# sensorNodev4.net
KiCad netlist of a schematic drawn in EAGLE
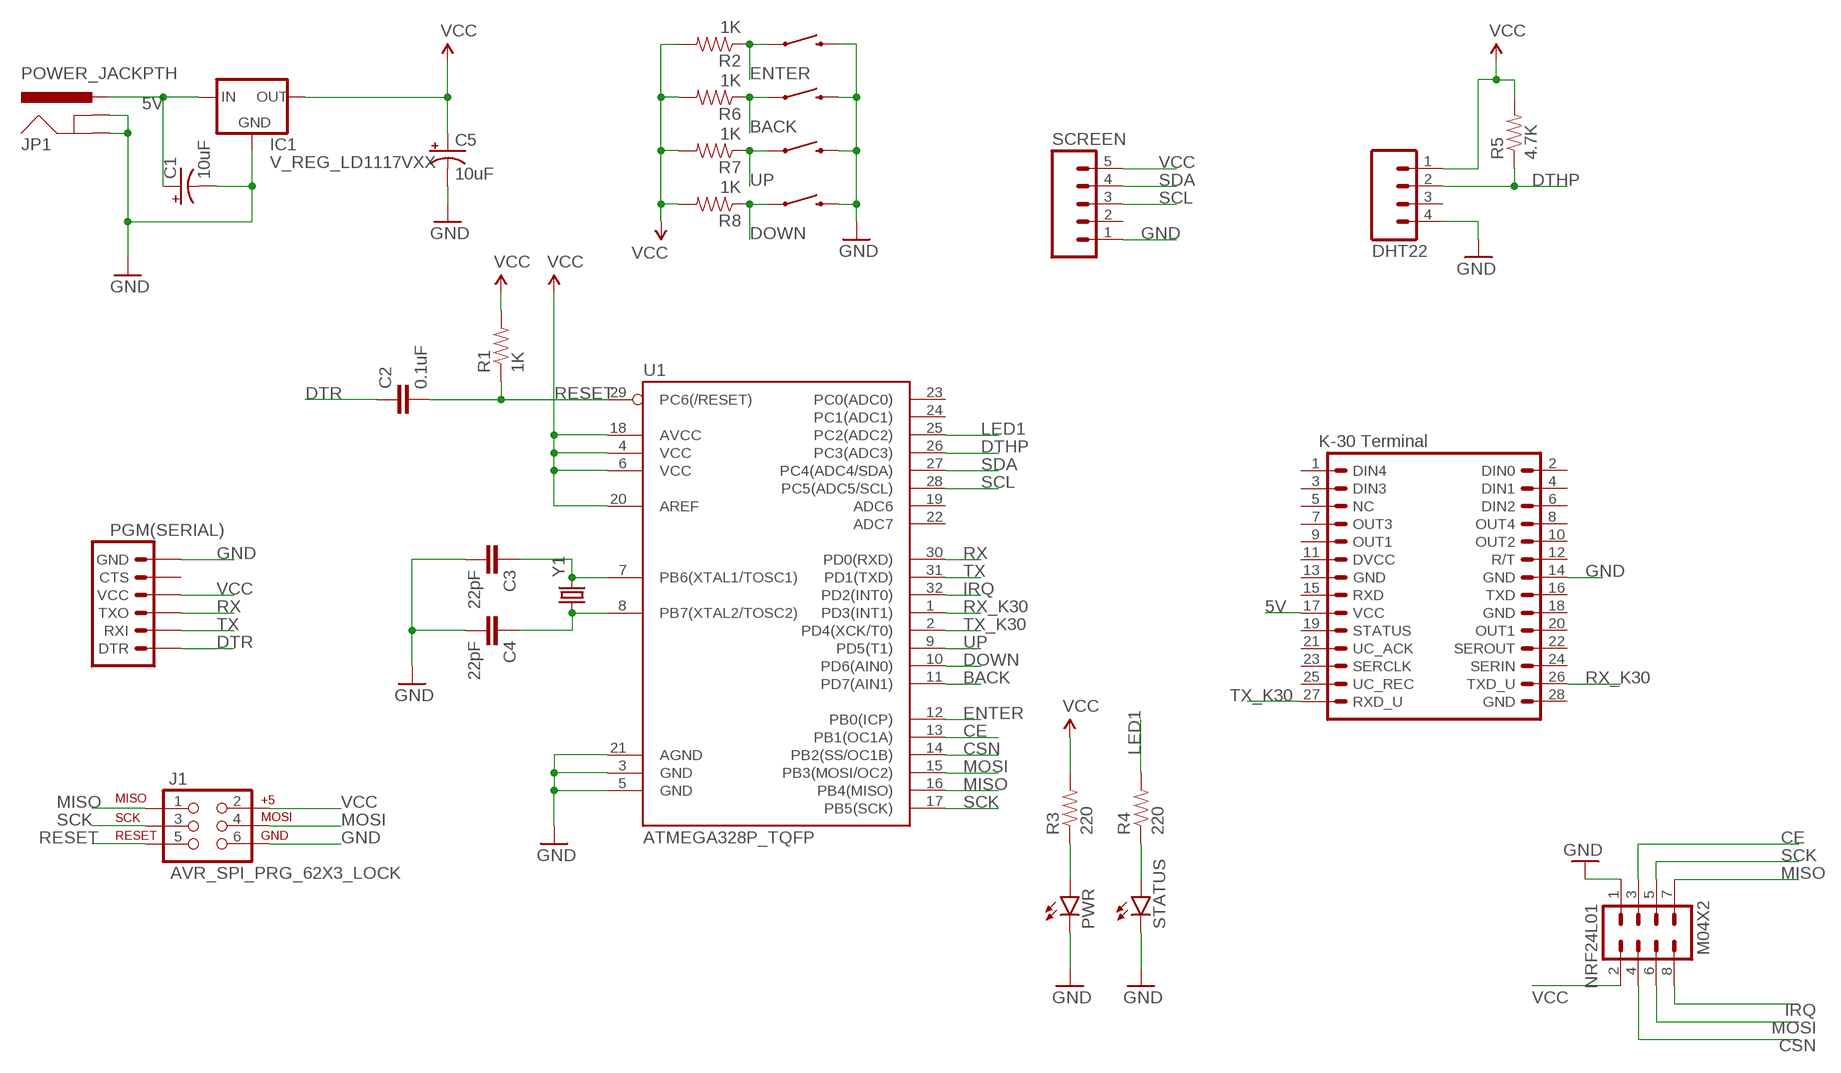
[diagram p0: schematic, sheet 1]

(export (version "E")
  (design (tool "Eeschema 10.0.6"))
  (components
    (comp (ref "BACK")
      (value "SWITCH-MOMENTARY-2PTH")
      (footprint "eagle-import:TACTILE-PTH")
      (libsource (lib "eagle-import") (part "SWITCH-MOMENTARY-2PTH"))
    )
    (comp (ref "C1")
      (value "10uF")
      (footprint "eagle-import:CPOL-RADIAL-10UF-25V")
      (libsource (lib "eagle-import") (part "CAP_POLPTH2"))
    )
    (comp (ref "C2")
      (value "0.1uF")
      (footprint "eagle-import:0603-CAP")
      (libsource (lib "eagle-import") (part "0.1UF-25V(+80/-20%)(0603)"))
    )
    (comp (ref "C3")
      (value "22pF")
      (footprint "eagle-import:0603-CAP")
      (libsource (lib "eagle-import") (part "22PF-50V-5%(0603)"))
    )
    (comp (ref "C4")
      (value "22pF")
      (footprint "eagle-import:0603-CAP")
      (libsource (lib "eagle-import") (part "22PF-50V-5%(0603)"))
    )
    (comp (ref "C5")
      (value "10uF")
      (footprint "eagle-import:CPOL-RADIAL-10UF-25V")
      (libsource (lib "eagle-import") (part "CAP_POLPTH2"))
    )
    (comp (ref "DHT22")
      (value "M04PTH")
      (footprint "eagle-import:1X04")
      (libsource (lib "eagle-import") (part "M04PTH"))
    )
    (comp (ref "DOWN")
      (value "SWITCH-MOMENTARY-2PTH")
      (footprint "eagle-import:TACTILE-PTH")
      (libsource (lib "eagle-import") (part "SWITCH-MOMENTARY-2PTH"))
    )
    (comp (ref "ENTER")
      (value "SWITCH-MOMENTARY-2PTH")
      (footprint "eagle-import:TACTILE-PTH")
      (libsource (lib "eagle-import") (part "SWITCH-MOMENTARY-2PTH"))
    )
    (comp (ref "IC1")
      (value "V_REG_LD1117VXX")
      (footprint "eagle-import:78XXL")
      (libsource (lib "eagle-import") (part "V_REG_LD1117VXX"))
    )
    (comp (ref "J1")
      (value "AVR_SPI_PRG_62X3_LOCK")
      (footprint "eagle-import:2X3_LOCK")
      (libsource (lib "eagle-import") (part "AVR_SPI_PRG_62X3_LOCK"))
    )
    (comp (ref "JP1")
      (value "POWER_JACKPTH")
      (footprint "eagle-import:POWER_JACK_PTH")
      (libsource (lib "eagle-import") (part "POWER_JACKPTH"))
    )
    (comp (ref "JP3")
      (value "K-30K-30")
      (footprint "eagle-import:K-30")
      (libsource (lib "eagle-import") (part "K-30K-30"))
    )
    (comp (ref "NRF24L01")
      (value "M04X2")
      (footprint "eagle-import:2X4")
      (libsource (lib "eagle-import") (part "M04X2"))
    )
    (comp (ref "PGM(SERIAL)")
      (value "ARDUINO_SERIAL_PROGRAMPTH")
      (footprint "eagle-import:1X06")
      (libsource (lib "eagle-import") (part "ARDUINO_SERIAL_PROGRAMPTH"))
    )
    (comp (ref "PWR")
      (value "LED0603")
      (footprint "eagle-import:LED-0603")
      (libsource (lib "eagle-import") (part "LED0603"))
    )
    (comp (ref "R1")
      (value "1K")
      (footprint "eagle-import:0603-RES")
      (libsource (lib "eagle-import") (part "1KOHM-1/10W-1%(0603)"))
    )
    (comp (ref "R2")
      (value "1K")
      (footprint "eagle-import:0603-RES")
      (libsource (lib "eagle-import") (part "1KOHM-1/10W-1%(0603)"))
    )
    (comp (ref "R3")
      (value "220")
      (footprint "eagle-import:0603-RES")
      (libsource (lib "eagle-import") (part "1KOHM-1/10W-1%(0603)"))
    )
    (comp (ref "R4")
      (value "220")
      (footprint "eagle-import:0603-RES")
      (libsource (lib "eagle-import") (part "1KOHM-1/10W-1%(0603)"))
    )
    (comp (ref "R5")
      (value "4.7K")
      (footprint "eagle-import:0603-RES")
      (libsource (lib "eagle-import") (part "1KOHM-1/10W-1%(0603)"))
    )
    (comp (ref "R6")
      (value "1K")
      (footprint "eagle-import:0603-RES")
      (libsource (lib "eagle-import") (part "1KOHM-1/10W-1%(0603)"))
    )
    (comp (ref "R7")
      (value "1K")
      (footprint "eagle-import:0603-RES")
      (libsource (lib "eagle-import") (part "1KOHM-1/10W-1%(0603)"))
    )
    (comp (ref "R8")
      (value "1K")
      (footprint "eagle-import:0603-RES")
      (libsource (lib "eagle-import") (part "1KOHM-1/10W-1%(0603)"))
    )
    (comp (ref "SCREEN")
      (value "M05PTH")
      (footprint "eagle-import:1X05")
      (libsource (lib "eagle-import") (part "M05PTH"))
    )
    (comp (ref "STATUS")
      (value "LED0603")
      (footprint "eagle-import:LED-0603")
      (libsource (lib "eagle-import") (part "LED0603"))
    )
    (comp (ref "U1")
      (value "ATMEGA328P_TQFP")
      (footprint "eagle-import:TQFP32-08")
      (libsource (lib "eagle-import") (part "ATMEGA328P_TQFP"))
    )
    (comp (ref "UP")
      (value "SWITCH-MOMENTARY-2PTH")
      (footprint "eagle-import:TACTILE-PTH")
      (libsource (lib "eagle-import") (part "SWITCH-MOMENTARY-2PTH"))
    )
    (comp (ref "Y1")
      (value "CRYSTALHC49US")
      (footprint "eagle-import:HC49US")
      (libsource (lib "eagle-import") (part "CRYSTALHC49US"))
    )
  )
  (nets
    (net (code "1") (name "/5V") (class "Default")
      (node (ref "C1") (pin "1") (pinfunction "+_1") (pintype "passive"))
      (node (ref "IC1") (pin "OUT") (pinfunction "IN_OUT") (pintype "input"))
      (node (ref "JP1") (pin "PWR") (pinfunction "PWR_PWR") (pintype "bidirectional"))
      (node (ref "JP3") (pin "17") (pinfunction "VCC_17") (pintype "bidirectional"))
    )
    (net (code "2") (name "/BACK") (class "Default")
      (node (ref "BACK") (pin "1") (pinfunction "1_1") (pintype "passive"))
      (node (ref "R6") (pin "1") (pinfunction "1_1") (pintype "passive"))
      (node (ref "U1") (pin "11") (pinfunction "PD7(AIN1)_11") (pintype "bidirectional"))
    )
    (net (code "3") (name "/CE") (class "Default")
      (node (ref "NRF24L01") (pin "3") (pinfunction "3_3") (pintype "passive"))
      (node (ref "U1") (pin "13") (pinfunction "PB1(OC1A)_13") (pintype "bidirectional"))
    )
    (net (code "4") (name "/CSN") (class "Default")
      (node (ref "NRF24L01") (pin "4") (pinfunction "4_4") (pintype "passive"))
      (node (ref "U1") (pin "14") (pinfunction "PB2(SS/OC1B)_14") (pintype "bidirectional"))
    )
    (net (code "5") (name "/DOWN") (class "Default")
      (node (ref "DOWN") (pin "1") (pinfunction "1_1") (pintype "passive"))
      (node (ref "R8") (pin "1") (pinfunction "1_1") (pintype "passive"))
      (node (ref "U1") (pin "10") (pinfunction "PD6(AIN0)_10") (pintype "bidirectional"))
    )
    (net (code "6") (name "/DTHP") (class "Default")
      (node (ref "DHT22") (pin "2") (pinfunction "2_2") (pintype "passive"))
      (node (ref "R5") (pin "1") (pinfunction "1_1") (pintype "passive"))
      (node (ref "U1") (pin "26") (pinfunction "PC3(ADC3)_26") (pintype "bidirectional"))
    )
    (net (code "7") (name "/DTR") (class "Default")
      (node (ref "C2") (pin "1") (pinfunction "1_1") (pintype "passive"))
      (node (ref "PGM(SERIAL)") (pin "1") (pinfunction "DTR_1") (pintype "passive"))
    )
    (net (code "8") (name "/ENTER") (class "Default")
      (node (ref "ENTER") (pin "1") (pinfunction "1_1") (pintype "passive"))
      (node (ref "R2") (pin "1") (pinfunction "1_1") (pintype "passive"))
      (node (ref "U1") (pin "12") (pinfunction "PB0(ICP)_12") (pintype "bidirectional"))
    )
    (net (code "9") (name "/IRQ") (class "Default")
      (node (ref "NRF24L01") (pin "8") (pinfunction "8_8") (pintype "passive"))
      (node (ref "U1") (pin "32") (pinfunction "PD2(INT0)_32") (pintype "bidirectional"))
    )
    (net (code "10") (name "/LED1") (class "Default")
      (node (ref "R4") (pin "2") (pinfunction "2_2") (pintype "passive"))
      (node (ref "U1") (pin "25") (pinfunction "PC2(ADC2)_25") (pintype "bidirectional"))
    )
    (net (code "11") (name "/MISO") (class "Default")
      (node (ref "J1") (pin "1") (pinfunction "1_1") (pintype "passive"))
      (node (ref "NRF24L01") (pin "7") (pinfunction "7_7") (pintype "passive"))
      (node (ref "U1") (pin "16") (pinfunction "PB4(MISO)_16") (pintype "bidirectional"))
    )
    (net (code "12") (name "/MOSI") (class "Default")
      (node (ref "J1") (pin "4") (pinfunction "4_4") (pintype "passive"))
      (node (ref "NRF24L01") (pin "6") (pinfunction "6_6") (pintype "passive"))
      (node (ref "U1") (pin "15") (pinfunction "PB3(MOSI/OC2)_15") (pintype "bidirectional"))
    )
    (net (code "13") (name "/RESET") (class "Default")
      (node (ref "C2") (pin "2") (pinfunction "2_2") (pintype "passive"))
      (node (ref "J1") (pin "5") (pinfunction "5_5") (pintype "passive"))
      (node (ref "R1") (pin "1") (pinfunction "1_1") (pintype "passive"))
      (node (ref "U1") (pin "29") (pinfunction "PC6(/RESET)_29") (pintype "bidirectional"))
    )
    (net (code "14") (name "/RX") (class "Default")
      (node (ref "PGM(SERIAL)") (pin "3") (pinfunction "TXO_3") (pintype "passive"))
      (node (ref "U1") (pin "30") (pinfunction "PD0(RXD)_30") (pintype "bidirectional"))
    )
    (net (code "15") (name "/RX_K30") (class "Default")
      (node (ref "JP3") (pin "26") (pinfunction "TXD_U_26") (pintype "bidirectional"))
      (node (ref "U1") (pin "1") (pinfunction "PD3(INT1)_1") (pintype "bidirectional"))
    )
    (net (code "16") (name "/SCK") (class "Default")
      (node (ref "J1") (pin "3") (pinfunction "3_3") (pintype "passive"))
      (node (ref "NRF24L01") (pin "5") (pinfunction "5_5") (pintype "passive"))
      (node (ref "U1") (pin "17") (pinfunction "PB5(SCK)_17") (pintype "bidirectional"))
    )
    (net (code "17") (name "/SCL") (class "Default")
      (node (ref "SCREEN") (pin "3") (pinfunction "3_3") (pintype "passive"))
      (node (ref "U1") (pin "28") (pinfunction "PC5(ADC5/SCL)_28") (pintype "bidirectional"))
    )
    (net (code "18") (name "/SDA") (class "Default")
      (node (ref "SCREEN") (pin "4") (pinfunction "4_4") (pintype "passive"))
      (node (ref "U1") (pin "27") (pinfunction "PC4(ADC4/SDA)_27") (pintype "bidirectional"))
    )
    (net (code "19") (name "/TX") (class "Default")
      (node (ref "PGM(SERIAL)") (pin "2") (pinfunction "RXI_2") (pintype "passive"))
      (node (ref "U1") (pin "31") (pinfunction "PD1(TXD)_31") (pintype "bidirectional"))
    )
    (net (code "20") (name "/TX_K30") (class "Default")
      (node (ref "JP3") (pin "27") (pinfunction "RXD_U_27") (pintype "bidirectional"))
      (node (ref "U1") (pin "2") (pinfunction "PD4(XCK/T0)_2") (pintype "bidirectional"))
    )
    (net (code "21") (name "/UP") (class "Default")
      (node (ref "R7") (pin "1") (pinfunction "1_1") (pintype "passive"))
      (node (ref "U1") (pin "9") (pinfunction "PD5(T1)_9") (pintype "bidirectional"))
      (node (ref "UP") (pin "1") (pinfunction "1_1") (pintype "passive"))
    )
    (net (code "22") (name "GND") (class "Default")
      (node (ref "BACK") (pin "3") (pinfunction "2_3") (pintype "passive"))
      (node (ref "C1") (pin "2") (pinfunction "-_2") (pintype "passive"))
      (node (ref "C3") (pin "2") (pinfunction "2_2") (pintype "passive"))
      (node (ref "C4") (pin "2") (pinfunction "2_2") (pintype "passive"))
      (node (ref "C5") (pin "2") (pinfunction "-_2") (pintype "passive"))
      (node (ref "DHT22") (pin "4") (pinfunction "4_4") (pintype "passive"))
      (node (ref "DOWN") (pin "3") (pinfunction "2_3") (pintype "passive"))
      (node (ref "ENTER") (pin "3") (pinfunction "2_3") (pintype "passive"))
      (node (ref "IC1") (pin "IN") (pinfunction "GND_IN") (pintype "input"))
      (node (ref "J1") (pin "6") (pinfunction "6_6") (pintype "passive"))
      (node (ref "JP1") (pin "GND") (pinfunction "GND_GND") (pintype "bidirectional"))
      (node (ref "JP1") (pin "GNDBREAK") (pinfunction "GNDBREAK_GNDBREAK") (pintype "bidirectional"))
      (node (ref "JP3") (pin "14") (pinfunction "GND_14") (pintype "bidirectional"))
      (node (ref "NRF24L01") (pin "1") (pinfunction "1_1") (pintype "passive"))
      (node (ref "PGM(SERIAL)") (pin "6") (pinfunction "GND_6") (pintype "passive"))
      (node (ref "PWR") (pin "C") (pinfunction "C_C") (pintype "passive"))
      (node (ref "SCREEN") (pin "1") (pinfunction "1_1") (pintype "passive"))
      (node (ref "STATUS") (pin "C") (pinfunction "C_C") (pintype "passive"))
      (node (ref "U1") (pin "21") (pinfunction "AGND_21") (pintype "bidirectional"))
      (node (ref "U1") (pin "3") (pinfunction "GND_3") (pintype "bidirectional"))
      (node (ref "U1") (pin "5") (pinfunction "GND_5") (pintype "bidirectional"))
      (node (ref "UP") (pin "3") (pinfunction "2_3") (pintype "passive"))
    )
    (net (code "23") (name "Net-(PWR-PadA)") (class "Default")
      (node (ref "PWR") (pin "A") (pinfunction "A_A") (pintype "passive"))
      (node (ref "R3") (pin "1") (pinfunction "1_1") (pintype "passive"))
    )
    (net (code "24") (name "Net-(R4-Pad1)") (class "Default")
      (node (ref "R4") (pin "1") (pinfunction "1_1") (pintype "passive"))
      (node (ref "STATUS") (pin "A") (pinfunction "A_A") (pintype "passive"))
    )
    (net (code "25") (name "Net-(U1-PB6(XTAL1{slash}TOSC1))") (class "Default")
      (node (ref "C3") (pin "1") (pinfunction "1_1") (pintype "passive"))
      (node (ref "U1") (pin "7") (pinfunction "PB6(XTAL1/TOSC1)_7") (pintype "bidirectional"))
      (node (ref "Y1") (pin "2") (pinfunction "2_2") (pintype "passive"))
    )
    (net (code "26") (name "Net-(U1-PB7(XTAL2{slash}TOSC2))") (class "Default")
      (node (ref "C4") (pin "1") (pinfunction "1_1") (pintype "passive"))
      (node (ref "U1") (pin "8") (pinfunction "PB7(XTAL2/TOSC2)_8") (pintype "bidirectional"))
      (node (ref "Y1") (pin "1") (pinfunction "1_1") (pintype "passive"))
    )
    (net (code "27") (name "VCC") (class "Default")
      (node (ref "C5") (pin "1") (pinfunction "+_1") (pintype "passive"))
      (node (ref "DHT22") (pin "1") (pinfunction "1_1") (pintype "passive"))
      (node (ref "IC1") (pin "GND") (pinfunction "OUT_GND") (pintype "output"))
      (node (ref "J1") (pin "2") (pinfunction "2_2") (pintype "passive"))
      (node (ref "NRF24L01") (pin "2") (pinfunction "2_2") (pintype "passive"))
      (node (ref "PGM(SERIAL)") (pin "4") (pinfunction "VCC_4") (pintype "passive"))
      (node (ref "R1") (pin "2") (pinfunction "2_2") (pintype "passive"))
      (node (ref "R2") (pin "2") (pinfunction "2_2") (pintype "passive"))
      (node (ref "R3") (pin "2") (pinfunction "2_2") (pintype "passive"))
      (node (ref "R5") (pin "2") (pinfunction "2_2") (pintype "passive"))
      (node (ref "R6") (pin "2") (pinfunction "2_2") (pintype "passive"))
      (node (ref "R7") (pin "2") (pinfunction "2_2") (pintype "passive"))
      (node (ref "R8") (pin "2") (pinfunction "2_2") (pintype "passive"))
      (node (ref "SCREEN") (pin "5") (pinfunction "5_5") (pintype "passive"))
      (node (ref "U1") (pin "18") (pinfunction "AVCC_18") (pintype "bidirectional"))
      (node (ref "U1") (pin "20") (pinfunction "AREF_20") (pintype "bidirectional"))
      (node (ref "U1") (pin "4") (pinfunction "VCC_4") (pintype "bidirectional"))
      (node (ref "U1") (pin "6") (pinfunction "VCC_6") (pintype "bidirectional"))
    )
    (net (code "28") (name "unconnected-(DHT22-Pad3)") (class "Default")
      (node (ref "DHT22") (pin "3") (pinfunction "3_3") (pintype "passive"))
    )
    (net (code "29") (name "unconnected-(JP3-DIN0-Pad2)") (class "Default")
      (node (ref "JP3") (pin "2") (pinfunction "DIN0_2") (pintype "bidirectional"))
    )
    (net (code "30") (name "unconnected-(JP3-DIN1-Pad4)") (class "Default")
      (node (ref "JP3") (pin "4") (pinfunction "DIN1_4") (pintype "bidirectional"))
    )
    (net (code "31") (name "unconnected-(JP3-DIN2-Pad6)") (class "Default")
      (node (ref "JP3") (pin "6") (pinfunction "DIN2_6") (pintype "bidirectional"))
    )
    (net (code "32") (name "unconnected-(JP3-DIN3-Pad3)") (class "Default")
      (node (ref "JP3") (pin "3") (pinfunction "DIN3_3") (pintype "bidirectional"))
    )
    (net (code "33") (name "unconnected-(JP3-DIN4-Pad1)") (class "Default")
      (node (ref "JP3") (pin "1") (pinfunction "DIN4_1") (pintype "bidirectional"))
    )
    (net (code "34") (name "unconnected-(JP3-DVCC-Pad11)") (class "Default")
      (node (ref "JP3") (pin "11") (pinfunction "DVCC_11") (pintype "bidirectional"))
    )
    (net (code "35") (name "unconnected-(JP3-GND-Pad13)") (class "Default")
      (node (ref "JP3") (pin "13") (pinfunction "GND_13") (pintype "bidirectional"))
    )
    (net (code "36") (name "unconnected-(JP3-GND-Pad18)") (class "Default")
      (node (ref "JP3") (pin "18") (pinfunction "GND_18") (pintype "bidirectional"))
    )
    (net (code "37") (name "unconnected-(JP3-GND-Pad28)") (class "Default")
      (node (ref "JP3") (pin "28") (pinfunction "GND_28") (pintype "bidirectional"))
    )
    (net (code "38") (name "unconnected-(JP3-NC-Pad5)") (class "Default")
      (node (ref "JP3") (pin "5") (pinfunction "NC_5") (pintype "bidirectional"))
    )
    (net (code "39") (name "unconnected-(JP3-OUT1-Pad9)") (class "Default")
      (node (ref "JP3") (pin "9") (pinfunction "OUT1_9") (pintype "bidirectional"))
    )
    (net (code "40") (name "unconnected-(JP3-OUT1-Pad20)") (class "Default")
      (node (ref "JP3") (pin "20") (pinfunction "OUT1_20") (pintype "bidirectional"))
    )
    (net (code "41") (name "unconnected-(JP3-OUT2-Pad10)") (class "Default")
      (node (ref "JP3") (pin "10") (pinfunction "OUT2_10") (pintype "bidirectional"))
    )
    (net (code "42") (name "unconnected-(JP3-OUT3-Pad7)") (class "Default")
      (node (ref "JP3") (pin "7") (pinfunction "OUT3_7") (pintype "bidirectional"))
    )
    (net (code "43") (name "unconnected-(JP3-OUT4-Pad8)") (class "Default")
      (node (ref "JP3") (pin "8") (pinfunction "OUT4_8") (pintype "bidirectional"))
    )
    (net (code "44") (name "unconnected-(JP3-RXD-Pad15)") (class "Default")
      (node (ref "JP3") (pin "15") (pinfunction "RXD_15") (pintype "bidirectional"))
    )
    (net (code "45") (name "unconnected-(JP3-R{slash}T-Pad12)") (class "Default")
      (node (ref "JP3") (pin "12") (pinfunction "R/T_12") (pintype "bidirectional"))
    )
    (net (code "46") (name "unconnected-(JP3-SERCLK-Pad23)") (class "Default")
      (node (ref "JP3") (pin "23") (pinfunction "SERCLK_23") (pintype "bidirectional"))
    )
    (net (code "47") (name "unconnected-(JP3-SERIN-Pad24)") (class "Default")
      (node (ref "JP3") (pin "24") (pinfunction "SERIN_24") (pintype "bidirectional"))
    )
    (net (code "48") (name "unconnected-(JP3-SEROUT-Pad22)") (class "Default")
      (node (ref "JP3") (pin "22") (pinfunction "SEROUT_22") (pintype "bidirectional"))
    )
    (net (code "49") (name "unconnected-(JP3-STATUS-Pad19)") (class "Default")
      (node (ref "JP3") (pin "19") (pinfunction "STATUS_19") (pintype "bidirectional"))
    )
    (net (code "50") (name "unconnected-(JP3-TXD-Pad16)") (class "Default")
      (node (ref "JP3") (pin "16") (pinfunction "TXD_16") (pintype "bidirectional"))
    )
    (net (code "51") (name "unconnected-(JP3-UC_ACK-Pad21)") (class "Default")
      (node (ref "JP3") (pin "21") (pinfunction "UC_ACK_21") (pintype "bidirectional"))
    )
    (net (code "52") (name "unconnected-(JP3-UC_REC-Pad25)") (class "Default")
      (node (ref "JP3") (pin "25") (pinfunction "UC_REC_25") (pintype "bidirectional"))
    )
    (net (code "53") (name "unconnected-(PGM(SERIAL)-CTS-Pad5)") (class "Default")
      (node (ref "PGM(SERIAL)") (pin "5") (pinfunction "CTS_5") (pintype "passive"))
    )
    (net (code "54") (name "unconnected-(SCREEN-Pad2)") (class "Default")
      (node (ref "SCREEN") (pin "2") (pinfunction "2_2") (pintype "passive"))
    )
    (net (code "55") (name "unconnected-(U1-ADC6-Pad19)") (class "Default")
      (node (ref "U1") (pin "19") (pinfunction "ADC6_19") (pintype "bidirectional"))
    )
    (net (code "56") (name "unconnected-(U1-ADC7-Pad22)") (class "Default")
      (node (ref "U1") (pin "22") (pinfunction "ADC7_22") (pintype "bidirectional"))
    )
    (net (code "57") (name "unconnected-(U1-PC0(ADC0)-Pad23)") (class "Default")
      (node (ref "U1") (pin "23") (pinfunction "PC0(ADC0)_23") (pintype "bidirectional"))
    )
    (net (code "58") (name "unconnected-(U1-PC1(ADC1)-Pad24)") (class "Default")
      (node (ref "U1") (pin "24") (pinfunction "PC1(ADC1)_24") (pintype "bidirectional"))
    )
  )
)
